# FPGA.net
KiCad netlist of a schematic drawn in Altium Designer
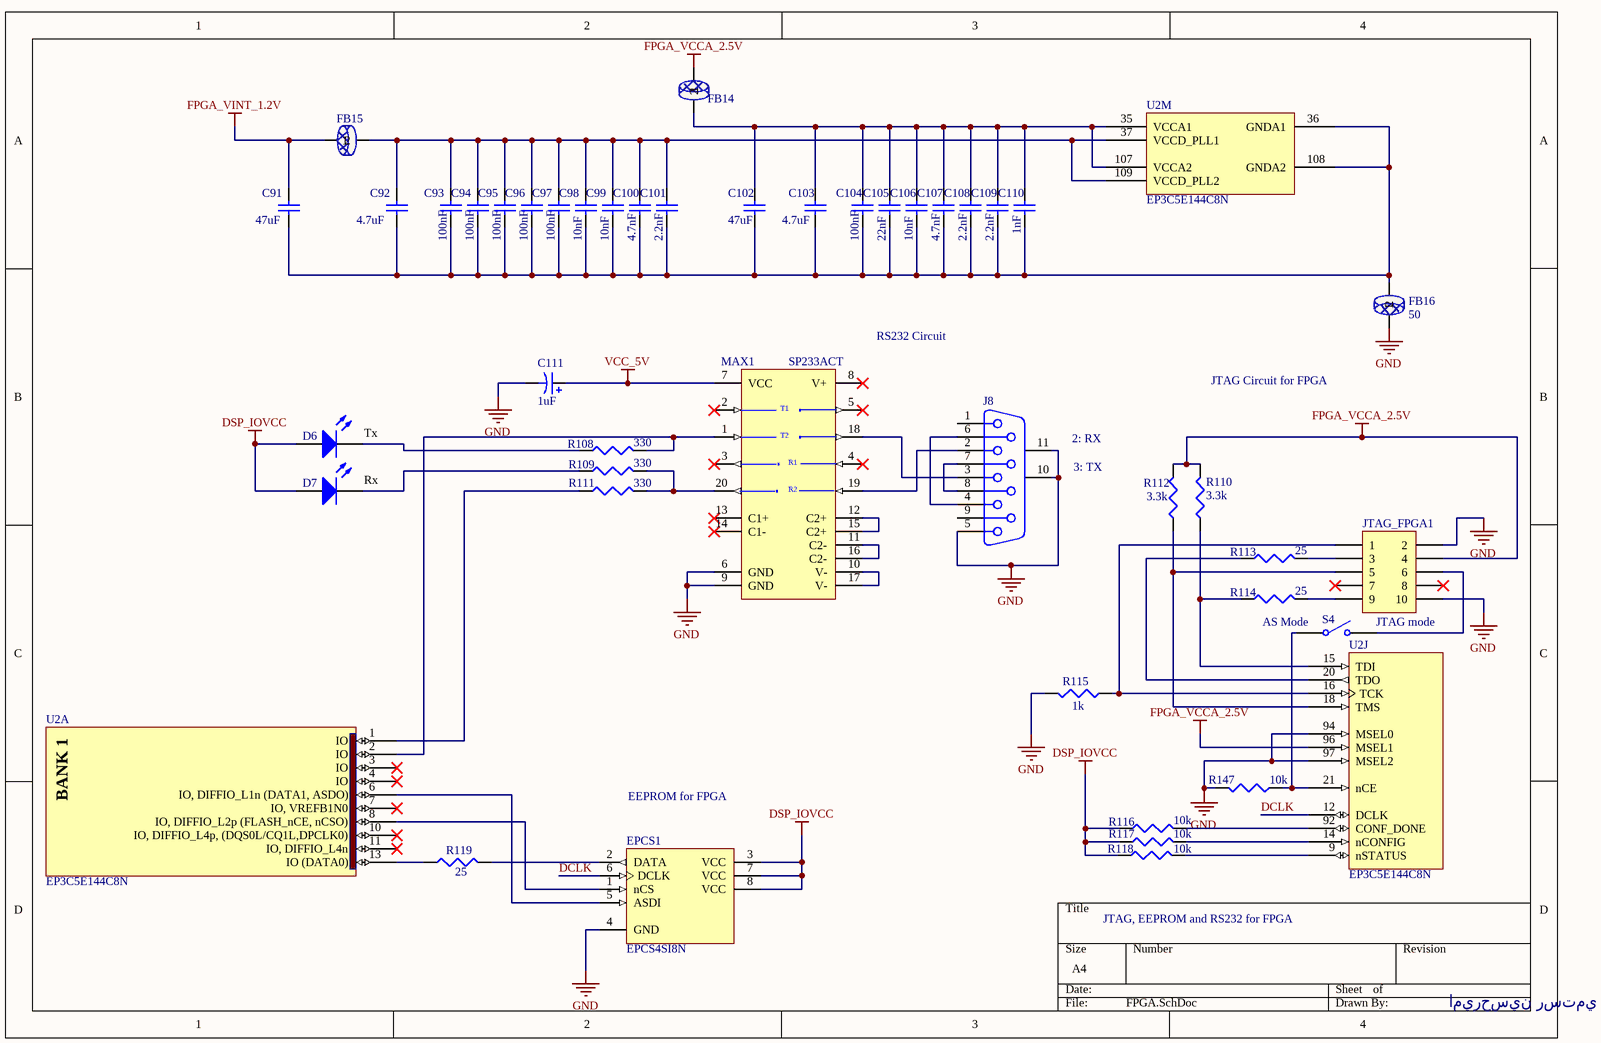
[diagram p0: FPGA.SchDoc]

(export (version "E")
  (design (tool "Eeschema 10.0.6"))
  (components
    (comp (ref "C91")
      (value "47uF")
      (footprint "C1206")
      (description "Capacitor")
      (fields (field (name "Comment") "470uF") (field (name "PUBLISHER") "Altium Limited"))
      (libsource (lib "Miscellaneous Devices") (part "Cap Semi"))
    )
    (comp (ref "C92")
      (value "4.7uF")
      (footprint "1608[0603]")
      (description "Capacitor")
      (fields (field (name "PUBLISHER") "Altium Limited"))
      (libsource (lib "Miscellaneous Devices") (part "Cap Semi"))
    )
    (comp (ref "C93")
      (value "100nF")
      (footprint "1608[0603]")
      (description "Capacitor")
      (fields (field (name "PUBLISHER") "Altium Limited"))
      (libsource (lib "Miscellaneous Devices") (part "Cap Semi"))
    )
    (comp (ref "C94")
      (value "100nF")
      (footprint "1608[0603]")
      (description "Capacitor")
      (fields (field (name "PUBLISHER") "Altium Limited"))
      (libsource (lib "Miscellaneous Devices") (part "Cap Semi"))
    )
    (comp (ref "C95")
      (value "100nF")
      (footprint "1608[0603]")
      (description "Capacitor")
      (fields (field (name "PUBLISHER") "Altium Limited"))
      (libsource (lib "Miscellaneous Devices") (part "Cap Semi"))
    )
    (comp (ref "C96")
      (value "100nF")
      (footprint "1608[0603]")
      (description "Capacitor")
      (fields (field (name "PUBLISHER") "Altium Limited"))
      (libsource (lib "Miscellaneous Devices") (part "Cap Semi"))
    )
    (comp (ref "C97")
      (value "100nF")
      (footprint "1608[0603]")
      (description "Capacitor")
      (fields (field (name "PUBLISHER") "Altium Limited"))
      (libsource (lib "Miscellaneous Devices") (part "Cap Semi"))
    )
    (comp (ref "C98")
      (value "10nF")
      (footprint "1608[0603]")
      (description "Capacitor")
      (fields (field (name "PUBLISHER") "Altium Limited"))
      (libsource (lib "Miscellaneous Devices") (part "Cap Semi"))
    )
    (comp (ref "C99")
      (value "10nF")
      (footprint "1608[0603]")
      (description "Capacitor")
      (fields (field (name "PUBLISHER") "Altium Limited"))
      (libsource (lib "Miscellaneous Devices") (part "Cap Semi"))
    )
    (comp (ref "C100")
      (value "4.7nF")
      (footprint "1608[0603]")
      (description "Capacitor")
      (fields (field (name "PUBLISHER") "Altium Limited"))
      (libsource (lib "Miscellaneous Devices") (part "Cap Semi"))
    )
    (comp (ref "C101")
      (value "2.2nF")
      (footprint "1608[0603]")
      (description "Capacitor")
      (fields (field (name "PUBLISHER") "Altium Limited"))
      (libsource (lib "Miscellaneous Devices") (part "Cap Semi"))
    )
    (comp (ref "C102")
      (value "47uF")
      (footprint "C1206")
      (description "Capacitor")
      (fields (field (name "PUBLISHER") "Altium Limited"))
      (libsource (lib "Miscellaneous Devices") (part "Cap Semi"))
    )
    (comp (ref "C103")
      (value "4.7uF")
      (footprint "1608[0603]")
      (description "Capacitor")
      (fields (field (name "PUBLISHER") "Altium Limited"))
      (libsource (lib "Miscellaneous Devices") (part "Cap Semi"))
    )
    (comp (ref "C104")
      (value "100nF")
      (footprint "1608[0603]")
      (description "Capacitor")
      (fields (field (name "PUBLISHER") "Altium Limited"))
      (libsource (lib "Miscellaneous Devices") (part "Cap Semi"))
    )
    (comp (ref "C105")
      (value "22nF")
      (footprint "1608[0603]")
      (description "Capacitor")
      (fields (field (name "PUBLISHER") "Altium Limited"))
      (libsource (lib "Miscellaneous Devices") (part "Cap Semi"))
    )
    (comp (ref "C106")
      (value "10nF")
      (footprint "1608[0603]")
      (description "Capacitor")
      (fields (field (name "PUBLISHER") "Altium Limited"))
      (libsource (lib "Miscellaneous Devices") (part "Cap Semi"))
    )
    (comp (ref "C107")
      (value "4.7nF")
      (footprint "1608[0603]")
      (description "Capacitor")
      (fields (field (name "PUBLISHER") "Altium Limited"))
      (libsource (lib "Miscellaneous Devices") (part "Cap Semi"))
    )
    (comp (ref "C108")
      (value "2.2nF")
      (footprint "1608[0603]")
      (description "Capacitor")
      (fields (field (name "PUBLISHER") "Altium Limited"))
      (libsource (lib "Miscellaneous Devices") (part "Cap Semi"))
    )
    (comp (ref "C109")
      (value "2.2nF")
      (footprint "1608[0603]")
      (description "Capacitor")
      (fields (field (name "PUBLISHER") "Altium Limited"))
      (libsource (lib "Miscellaneous Devices") (part "Cap Semi"))
    )
    (comp (ref "C110")
      (value "1nF")
      (footprint "1608[0603]")
      (description "Capacitor")
      (fields (field (name "PUBLISHER") "Altium Limited"))
      (libsource (lib "Miscellaneous Devices") (part "Cap Semi"))
    )
    (comp (ref "C111")
      (value "1uF")
      (footprint "C1206")
      (description "Polarized Capacitor")
      (fields (field (name "PUBLISHER") "Altium Limited"))
      (libsource (lib "Miscellaneous Devices") (part "Cap Pol3"))
    )
    (comp (ref "D6")
      (value "Yellow")
      (footprint "1.6X0.8X0.4")
      (description "LED")
      (fields (field (name "PUBLISHER") "Altium Limited"))
      (libsource (lib "Miscellaneous Devices") (part "LED3"))
    )
    (comp (ref "D7")
      (value "Yellow")
      (footprint "1.6X0.8X0.4")
      (description "LED")
      (fields (field (name "PUBLISHER") "Altium Limited"))
      (libsource (lib "Miscellaneous Devices") (part "LED3"))
    )
    (comp (ref "EPCS1")
      (value "EPCS4SI8N")
      (footprint "SOIC8_M")
      (fields (field (name "PUBLISHER") "Altium Limited"))
      (libsource (lib "Altera EPCS Configuration Device") (part "EPCS4SI8N"))
    )
    (comp (ref "FB14")
      (value "Ferrite Bead")
      (footprint "Miscellaneous Devices:3216[1206]")
      (libsource (lib "") (part "Ferrite Bead_1"))
    )
    (comp (ref "FB15")
      (value "50")
      (footprint "Miscellaneous Devices:3216[1206]")
      (description "Ferrite Bead")
      (libsource (lib "ferrite_bead") (part "Ferrite Bead"))
    )
    (comp (ref "FB16")
      (value "50")
      (footprint "Miscellaneous Devices:3216[1206]")
      (description "Ferrite Bead")
      (libsource (lib "") (part "Ferrite Bead_2"))
    )
    (comp (ref "J8")
      (value "D Connector 9")
      (footprint "DSUB1.385-2H9")
      (description "Receptacle Assembly, 9 Position, Right Angle")
      (fields (field (name "PUBLISHER") "Altium Limited"))
      (libsource (lib "Miscellaneous Connectors") (part "D Connector 9"))
    )
    (comp (ref "JTAG_FPGA1")
      (value "Header 5X2")
      (footprint "HDR2X5")
      (description "Header, 5-Pin, Dual row")
      (fields (field (name "PUBLISHER") "Altium Limited"))
      (libsource (lib "Miscellaneous Connectors") (part "Header 5X2"))
    )
    (comp (ref "MAX1")
      (value "SP233ACT")
      (footprint "WSO20_L")
      (description "+5V-Powered, Multichannel RS-232 Driver/Receiver")
      (fields (field (name "PUBLISHER") "Altium Limited"))
      (libsource (lib "Maxim Communication Transceiver") (part "MAX233AEWP"))
    )
    (comp (ref "R108")
      (value "330")
      (footprint "J1-0603")
      (description "Resistor")
      (fields (field (name "PUBLISHER") "Altium Limited"))
      (libsource (lib "Miscellaneous Devices") (part "Res3"))
    )
    (comp (ref "R109")
      (value "330")
      (footprint "J1-0603")
      (description "Resistor")
      (fields (field (name "PUBLISHER") "Altium Limited"))
      (libsource (lib "Miscellaneous Devices") (part "Res3"))
    )
    (comp (ref "R110")
      (value "3.3k")
      (footprint "J1-0603")
      (description "Resistor")
      (fields (field (name "PUBLISHER") "Altium Limited"))
      (libsource (lib "Miscellaneous Devices") (part "Res3"))
    )
    (comp (ref "R111")
      (value "330")
      (footprint "J1-0603")
      (description "Resistor")
      (fields (field (name "PUBLISHER") "Altium Limited"))
      (libsource (lib "Miscellaneous Devices") (part "Res3"))
    )
    (comp (ref "R112")
      (value "3.3k")
      (footprint "J1-0603")
      (description "Resistor")
      (fields (field (name "PUBLISHER") "Altium Limited"))
      (libsource (lib "Miscellaneous Devices") (part "Res3"))
    )
    (comp (ref "R113")
      (value "25")
      (footprint "J1-0603")
      (description "Resistor")
      (fields (field (name "PUBLISHER") "Altium Limited"))
      (libsource (lib "Miscellaneous Devices") (part "Res3"))
    )
    (comp (ref "R114")
      (value "25")
      (footprint "J1-0603")
      (description "Resistor")
      (fields (field (name "PUBLISHER") "Altium Limited"))
      (libsource (lib "Miscellaneous Devices") (part "Res3"))
    )
    (comp (ref "R115")
      (value "1k")
      (footprint "J1-0603")
      (description "Resistor")
      (fields (field (name "PUBLISHER") "Altium Limited"))
      (libsource (lib "Miscellaneous Devices") (part "Res3"))
    )
    (comp (ref "R116")
      (value "10k")
      (footprint "J1-0603")
      (description "Resistor")
      (fields (field (name "PUBLISHER") "Altium Limited"))
      (libsource (lib "Miscellaneous Devices") (part "Res3"))
    )
    (comp (ref "R117")
      (value "10k")
      (footprint "J1-0603")
      (description "Resistor")
      (fields (field (name "PUBLISHER") "Altium Limited"))
      (libsource (lib "Miscellaneous Devices") (part "Res3"))
    )
    (comp (ref "R118")
      (value "10k")
      (footprint "J1-0603")
      (description "Resistor")
      (fields (field (name "PUBLISHER") "Altium Limited"))
      (libsource (lib "Miscellaneous Devices") (part "Res3"))
    )
    (comp (ref "R119")
      (value "25")
      (footprint "J1-0603")
      (description "Resistor")
      (fields (field (name "PUBLISHER") "Altium Limited"))
      (libsource (lib "Miscellaneous Devices") (part "Res3"))
    )
    (comp (ref "R147")
      (value "10k")
      (footprint "J1-0603")
      (description "Resistor")
      (fields (field (name "PUBLISHER") "Altium Limited"))
      (libsource (lib "Miscellaneous Devices") (part "Res3"))
    )
    (comp (ref "S4")
      (value "SW-SPST")
      (footprint "DIP_SW_1")
      (description "Single-Pole, Single-Throw Switch")
      (fields (field (name "PUBLISHER") "Altium Limited"))
      (libsource (lib "Miscellaneous Devices") (part "SW-SPST"))
    )
    (comp (ref "U2")
      (value "EP3C5E144C8N")
      (footprint "EQFP144_N")
      (fields (field (name "PUBLISHER") "Altium Limited"))
      (libsource (lib "Altera Cyclone III") (part "EP3C5E144C8N"))
    )
  )
  (nets
    (net (code "1") (name "/DCLK") (class "Default")
      (node (ref "EPCS1") (pin "6") (pinfunction "DCLK_6") (pintype "input"))
      (node (ref "U2") (pin "12") (pinfunction "DCLK_12") (pintype "bidirectional"))
    )
    (net (code "2") (name "DSP_IOVCC") (class "Default")
      (node (ref "D6") (pin "1") (pinfunction "A_1") (pintype "passive"))
      (node (ref "D7") (pin "1") (pinfunction "A_1") (pintype "passive"))
      (node (ref "EPCS1") (pin "3") (pinfunction "VCC_3") (pintype "power_in"))
      (node (ref "EPCS1") (pin "7") (pinfunction "VCC_7") (pintype "power_in"))
      (node (ref "EPCS1") (pin "8") (pinfunction "VCC_8") (pintype "power_in"))
      (node (ref "R116") (pin "1") (pinfunction "1_1") (pintype "passive"))
      (node (ref "R117") (pin "1") (pinfunction "1_1") (pintype "passive"))
      (node (ref "R118") (pin "1") (pinfunction "1_1") (pintype "passive"))
    )
    (net (code "3") (name "FPGA_VCCA_2.5V") (class "Default")
      (node (ref "FB14") (pin "2") (pinfunction "2_2") (pintype "passive"))
      (node (ref "JTAG_FPGA1") (pin "4") (pinfunction "4_4") (pintype "passive"))
      (node (ref "R110") (pin "2") (pinfunction "2_2") (pintype "passive"))
      (node (ref "R112") (pin "2") (pinfunction "2_2") (pintype "passive"))
      (node (ref "U2") (pin "96") (pinfunction "MSEL1_96") (pintype "input"))
    )
    (net (code "4") (name "FPGA_VINT_1.2V") (class "Default")
      (node (ref "C91") (pin "1") (pinfunction "1_1") (pintype "passive"))
      (node (ref "FB15") (pin "2") (pinfunction "2_2") (pintype "passive"))
    )
    (net (code "5") (name "GND") (class "Default")
      (node (ref "C111") (pin "2") (pinfunction "2_2") (pintype "passive"))
      (node (ref "EPCS1") (pin "4") (pinfunction "GND_4") (pintype "power_in"))
      (node (ref "FB16") (pin "2") (pinfunction "2_2") (pintype "passive"))
      (node (ref "J8") (pin "10") (pinfunction "MH1_10") (pintype "passive"))
      (node (ref "J8") (pin "11") (pinfunction "MH2_11") (pintype "passive"))
      (node (ref "J8") (pin "5") (pinfunction "5_5") (pintype "passive"))
      (node (ref "JTAG_FPGA1") (pin "10") (pinfunction "10_10") (pintype "passive"))
      (node (ref "JTAG_FPGA1") (pin "2") (pinfunction "2_2") (pintype "passive"))
      (node (ref "MAX1") (pin "6") (pinfunction "GND_6") (pintype "power_in"))
      (node (ref "MAX1") (pin "9") (pinfunction "GND_9") (pintype "power_in"))
      (node (ref "R115") (pin "2") (pinfunction "2_2") (pintype "passive"))
      (node (ref "R147") (pin "2") (pinfunction "2_2") (pintype "passive"))
      (node (ref "U2") (pin "94") (pinfunction "MSEL0_94") (pintype "input"))
      (node (ref "U2") (pin "97") (pinfunction "MSEL2_97") (pintype "input"))
    )
    (net (code "6") (name "Net-(D6-K)") (class "Default")
      (node (ref "D6") (pin "2") (pinfunction "K_2") (pintype "passive"))
      (node (ref "R108") (pin "1") (pinfunction "1_1") (pintype "passive"))
    )
    (net (code "7") (name "Net-(D7-K)") (class "Default")
      (node (ref "D7") (pin "2") (pinfunction "K_2") (pintype "passive"))
      (node (ref "R109") (pin "1") (pinfunction "1_1") (pintype "passive"))
    )
    (net (code "8") (name "Net-(EPCS1-ASDI)") (class "Default")
      (node (ref "EPCS1") (pin "5") (pinfunction "ASDI_5") (pintype "input"))
      (node (ref "U2") (pin "6") (pinfunction "IO,_DIFFIO_L1n_(DATA1,_ASDO)_6") (pintype "bidirectional"))
    )
    (net (code "9") (name "Net-(EPCS1-DATA)") (class "Default")
      (node (ref "EPCS1") (pin "2") (pinfunction "DATA_2") (pintype "output"))
      (node (ref "R119") (pin "2") (pinfunction "2_2") (pintype "passive"))
    )
    (net (code "10") (name "Net-(EPCS1-nCS)") (class "Default")
      (node (ref "EPCS1") (pin "1") (pinfunction "nCS_1") (pintype "input"))
      (node (ref "U2") (pin "8") (pinfunction "IO,_DIFFIO_L2p_(FLASH_nCE,_nCSO)_8") (pintype "bidirectional"))
    )
    (net (code "11") (name "Net-(J8-Pad4)") (class "Default")
      (node (ref "J8") (pin "4") (pinfunction "4_4") (pintype "passive"))
      (node (ref "J8") (pin "6") (pinfunction "6_6") (pintype "passive"))
    )
    (net (code "12") (name "Net-(J8-Pad7)") (class "Default")
      (node (ref "J8") (pin "7") (pinfunction "7_7") (pintype "passive"))
      (node (ref "J8") (pin "8") (pinfunction "8_8") (pintype "passive"))
    )
    (net (code "13") (name "Net-(JTAG_FPGA1-Pad3)") (class "Default")
      (node (ref "JTAG_FPGA1") (pin "3") (pinfunction "3_3") (pintype "passive"))
      (node (ref "R113") (pin "2") (pinfunction "2_2") (pintype "passive"))
    )
    (net (code "14") (name "Net-(JTAG_FPGA1-Pad9)") (class "Default")
      (node (ref "JTAG_FPGA1") (pin "9") (pinfunction "9_9") (pintype "passive"))
      (node (ref "R114") (pin "2") (pinfunction "2_2") (pintype "passive"))
    )
    (net (code "15") (name "Net-(MAX1-C2+-Pad12)") (class "Default")
      (node (ref "MAX1") (pin "12") (pinfunction "C2+_12") (pintype "power_in"))
      (node (ref "MAX1") (pin "15") (pinfunction "C2+_15") (pintype "passive"))
    )
    (net (code "16") (name "Net-(MAX1-C2--Pad11)") (class "Default")
      (node (ref "MAX1") (pin "11") (pinfunction "C2-_11") (pintype "passive"))
      (node (ref "MAX1") (pin "16") (pinfunction "C2-_16") (pintype "passive"))
    )
    (net (code "17") (name "Net-(MAX1-R2IN)") (class "Default")
      (node (ref "J8") (pin "2") (pinfunction "2_2") (pintype "passive"))
      (node (ref "MAX1") (pin "19") (pinfunction "R2IN_19") (pintype "input"))
    )
    (net (code "18") (name "Net-(MAX1-R2OUT)") (class "Default")
      (node (ref "MAX1") (pin "20") (pinfunction "R2OUT_20") (pintype "output"))
      (node (ref "R109") (pin "2") (pinfunction "2_2") (pintype "passive"))
      (node (ref "R111") (pin "2") (pinfunction "2_2") (pintype "passive"))
    )
    (net (code "19") (name "Net-(MAX1-T2IN)") (class "Default")
      (node (ref "MAX1") (pin "1") (pinfunction "T2IN_1") (pintype "input"))
      (node (ref "R108") (pin "2") (pinfunction "2_2") (pintype "passive"))
      (node (ref "U2") (pin "2") (pinfunction "IO_2") (pintype "bidirectional"))
    )
    (net (code "20") (name "Net-(MAX1-T2OUT)") (class "Default")
      (node (ref "J8") (pin "3") (pinfunction "3_3") (pintype "passive"))
      (node (ref "MAX1") (pin "18") (pinfunction "T2OUT_18") (pintype "output"))
    )
    (net (code "21") (name "Net-(MAX1-V--Pad10)") (class "Default")
      (node (ref "MAX1") (pin "10") (pinfunction "V-_10") (pintype "passive"))
      (node (ref "MAX1") (pin "17") (pinfunction "V-_17") (pintype "power_in"))
    )
    (net (code "22") (name "Net-(R111-Pad1)") (class "Default")
      (node (ref "R111") (pin "1") (pinfunction "1_1") (pintype "passive"))
      (node (ref "U2") (pin "1") (pinfunction "IO_1") (pintype "bidirectional"))
    )
    (net (code "23") (name "Net-(S4-COMMON)") (class "Default")
      (node (ref "R147") (pin "1") (pinfunction "1_1") (pintype "passive"))
      (node (ref "S4") (pin "1") (pinfunction "COMMON_1") (pintype "passive"))
      (node (ref "U2") (pin "21") (pinfunction "nCE_21") (pintype "input"))
    )
    (net (code "24") (name "Net-(S4-NO)") (class "Default")
      (node (ref "JTAG_FPGA1") (pin "6") (pinfunction "6_6") (pintype "passive"))
      (node (ref "S4") (pin "2") (pinfunction "NO_2") (pintype "passive"))
    )
    (net (code "25") (name "Net-(U2A-IO_(DATA0))") (class "Default")
      (node (ref "R119") (pin "1") (pinfunction "1_1") (pintype "passive"))
      (node (ref "U2") (pin "13") (pinfunction "IO_(DATA0)_13") (pintype "bidirectional"))
    )
    (net (code "26") (name "Net-(U2J-CONF_DONE)") (class "Default")
      (node (ref "R116") (pin "2") (pinfunction "2_2") (pintype "passive"))
      (node (ref "U2") (pin "92") (pinfunction "CONF_DONE_92") (pintype "bidirectional"))
    )
    (net (code "27") (name "Net-(U2J-TCK)") (class "Default")
      (node (ref "JTAG_FPGA1") (pin "1") (pinfunction "1_1") (pintype "passive"))
      (node (ref "R115") (pin "1") (pinfunction "1_1") (pintype "passive"))
      (node (ref "U2") (pin "16") (pinfunction "TCK_16") (pintype "input"))
    )
    (net (code "28") (name "Net-(U2J-TDI)") (class "Default")
      (node (ref "R110") (pin "1") (pinfunction "1_1") (pintype "passive"))
      (node (ref "R114") (pin "1") (pinfunction "1_1") (pintype "passive"))
      (node (ref "U2") (pin "15") (pinfunction "TDI_15") (pintype "input"))
    )
    (net (code "29") (name "Net-(U2J-TDO)") (class "Default")
      (node (ref "R113") (pin "1") (pinfunction "1_1") (pintype "passive"))
      (node (ref "U2") (pin "20") (pinfunction "TDO_20") (pintype "output"))
    )
    (net (code "30") (name "Net-(U2J-TMS)") (class "Default")
      (node (ref "JTAG_FPGA1") (pin "5") (pinfunction "5_5") (pintype "passive"))
      (node (ref "R112") (pin "1") (pinfunction "1_1") (pintype "passive"))
      (node (ref "U2") (pin "18") (pinfunction "TMS_18") (pintype "input"))
    )
    (net (code "31") (name "Net-(U2J-nCONFIG)") (class "Default")
      (node (ref "R117") (pin "2") (pinfunction "2_2") (pintype "passive"))
      (node (ref "U2") (pin "14") (pinfunction "nCONFIG_14") (pintype "input"))
    )
    (net (code "32") (name "Net-(U2J-nSTATUS)") (class "Default")
      (node (ref "R118") (pin "2") (pinfunction "2_2") (pintype "passive"))
      (node (ref "U2") (pin "9") (pinfunction "nSTATUS_9") (pintype "bidirectional"))
    )
    (net (code "33") (name "Net-(U2M-GNDA1)") (class "Default")
      (node (ref "C100") (pin "2") (pinfunction "2_2") (pintype "passive"))
      (node (ref "C101") (pin "2") (pinfunction "2_2") (pintype "passive"))
      (node (ref "C102") (pin "2") (pinfunction "2_2") (pintype "passive"))
      (node (ref "C103") (pin "2") (pinfunction "2_2") (pintype "passive"))
      (node (ref "C104") (pin "2") (pinfunction "2_2") (pintype "passive"))
      (node (ref "C105") (pin "2") (pinfunction "2_2") (pintype "passive"))
      (node (ref "C106") (pin "2") (pinfunction "2_2") (pintype "passive"))
      (node (ref "C107") (pin "2") (pinfunction "2_2") (pintype "passive"))
      (node (ref "C108") (pin "2") (pinfunction "2_2") (pintype "passive"))
      (node (ref "C109") (pin "2") (pinfunction "2_2") (pintype "passive"))
      (node (ref "C110") (pin "2") (pinfunction "2_2") (pintype "passive"))
      (node (ref "C91") (pin "2") (pinfunction "2_2") (pintype "passive"))
      (node (ref "C92") (pin "2") (pinfunction "2_2") (pintype "passive"))
      (node (ref "C93") (pin "2") (pinfunction "2_2") (pintype "passive"))
      (node (ref "C94") (pin "2") (pinfunction "2_2") (pintype "passive"))
      (node (ref "C95") (pin "2") (pinfunction "2_2") (pintype "passive"))
      (node (ref "C96") (pin "2") (pinfunction "2_2") (pintype "passive"))
      (node (ref "C97") (pin "2") (pinfunction "2_2") (pintype "passive"))
      (node (ref "C98") (pin "2") (pinfunction "2_2") (pintype "passive"))
      (node (ref "C99") (pin "2") (pinfunction "2_2") (pintype "passive"))
      (node (ref "FB16") (pin "1") (pinfunction "1_1") (pintype "passive"))
      (node (ref "U2") (pin "108") (pinfunction "GNDA2_108") (pintype "power_in"))
      (node (ref "U2") (pin "36") (pinfunction "GNDA1_36") (pintype "power_in"))
    )
    (net (code "34") (name "Net-(U2M-VCCA1)") (class "Default")
      (node (ref "C102") (pin "1") (pinfunction "1_1") (pintype "passive"))
      (node (ref "C103") (pin "1") (pinfunction "1_1") (pintype "passive"))
      (node (ref "C104") (pin "1") (pinfunction "1_1") (pintype "passive"))
      (node (ref "C105") (pin "1") (pinfunction "1_1") (pintype "passive"))
      (node (ref "C106") (pin "1") (pinfunction "1_1") (pintype "passive"))
      (node (ref "C107") (pin "1") (pinfunction "1_1") (pintype "passive"))
      (node (ref "C108") (pin "1") (pinfunction "1_1") (pintype "passive"))
      (node (ref "C109") (pin "1") (pinfunction "1_1") (pintype "passive"))
      (node (ref "C110") (pin "1") (pinfunction "1_1") (pintype "passive"))
      (node (ref "FB14") (pin "1") (pinfunction "1_1") (pintype "passive"))
      (node (ref "U2") (pin "107") (pinfunction "VCCA2_107") (pintype "power_in"))
      (node (ref "U2") (pin "35") (pinfunction "VCCA1_35") (pintype "power_in"))
    )
    (net (code "35") (name "Net-(U2M-VCCD_PLL1)") (class "Default")
      (node (ref "C100") (pin "1") (pinfunction "1_1") (pintype "passive"))
      (node (ref "C101") (pin "1") (pinfunction "1_1") (pintype "passive"))
      (node (ref "C92") (pin "1") (pinfunction "1_1") (pintype "passive"))
      (node (ref "C93") (pin "1") (pinfunction "1_1") (pintype "passive"))
      (node (ref "C94") (pin "1") (pinfunction "1_1") (pintype "passive"))
      (node (ref "C95") (pin "1") (pinfunction "1_1") (pintype "passive"))
      (node (ref "C96") (pin "1") (pinfunction "1_1") (pintype "passive"))
      (node (ref "C97") (pin "1") (pinfunction "1_1") (pintype "passive"))
      (node (ref "C98") (pin "1") (pinfunction "1_1") (pintype "passive"))
      (node (ref "C99") (pin "1") (pinfunction "1_1") (pintype "passive"))
      (node (ref "FB15") (pin "1") (pinfunction "1_1") (pintype "passive"))
      (node (ref "U2") (pin "109") (pinfunction "VCCD_PLL2_109") (pintype "power_in"))
      (node (ref "U2") (pin "37") (pinfunction "VCCD_PLL1_37") (pintype "power_in"))
    )
    (net (code "36") (name "VCC_5V") (class "Default")
      (node (ref "C111") (pin "1") (pinfunction "1_1") (pintype "passive"))
      (node (ref "MAX1") (pin "7") (pinfunction "VCC_7") (pintype "power_in"))
    )
    (net (code "37") (name "unconnected-(J8-Pad1)") (class "Default")
      (node (ref "J8") (pin "1") (pinfunction "1_1") (pintype "passive"))
    )
    (net (code "38") (name "unconnected-(J8-Pad9)") (class "Default")
      (node (ref "J8") (pin "9") (pinfunction "9_9") (pintype "passive"))
    )
    (net (code "39") (name "unconnected-(JTAG_FPGA1-Pad7)") (class "Default")
      (node (ref "JTAG_FPGA1") (pin "7") (pinfunction "7_7") (pintype "passive+no_connect"))
    )
    (net (code "40") (name "unconnected-(JTAG_FPGA1-Pad8)") (class "Default")
      (node (ref "JTAG_FPGA1") (pin "8") (pinfunction "8_8") (pintype "passive+no_connect"))
    )
    (net (code "41") (name "unconnected-(MAX1-C1+-Pad13)") (class "Default")
      (node (ref "MAX1") (pin "13") (pinfunction "C1+_13") (pintype "passive+no_connect"))
    )
    (net (code "42") (name "unconnected-(MAX1-C1--Pad14)") (class "Default")
      (node (ref "MAX1") (pin "14") (pinfunction "C1-_14") (pintype "power_in+no_connect"))
    )
    (net (code "43") (name "unconnected-(MAX1-R1IN-Pad4)") (class "Default")
      (node (ref "MAX1") (pin "4") (pinfunction "R1IN_4") (pintype "input+no_connect"))
    )
    (net (code "44") (name "unconnected-(MAX1-R1OUT-Pad3)") (class "Default")
      (node (ref "MAX1") (pin "3") (pinfunction "R1OUT_3") (pintype "output+no_connect"))
    )
    (net (code "45") (name "unconnected-(MAX1-T1IN-Pad2)") (class "Default")
      (node (ref "MAX1") (pin "2") (pinfunction "T1IN_2") (pintype "input+no_connect"))
    )
    (net (code "46") (name "unconnected-(MAX1-T1OUT-Pad5)") (class "Default")
      (node (ref "MAX1") (pin "5") (pinfunction "T1OUT_5") (pintype "output+no_connect"))
    )
    (net (code "47") (name "unconnected-(MAX1-V+-Pad8)") (class "Default")
      (node (ref "MAX1") (pin "8") (pinfunction "V+_8") (pintype "passive+no_connect"))
    )
    (net (code "48") (name "unconnected-(U2A-IO,_DIFFIO_L4n-Pad11)") (class "Default")
      (node (ref "U2") (pin "11") (pinfunction "IO,_DIFFIO_L4n_11") (pintype "bidirectional+no_connect"))
    )
    (net (code "49") (name "unconnected-(U2A-IO,_DIFFIO_L4p,_(DQS0L{slash}CQ1L,DPCLK0)-Pad10)") (class "Default")
      (node (ref "U2") (pin "10") (pinfunction "IO,_DIFFIO_L4p,_(DQS0L/CQ1L,DPCLK0)_10") (pintype "bidirectional+no_connect"))
    )
    (net (code "50") (name "unconnected-(U2A-IO,_VREFB1N0-Pad7)") (class "Default")
      (node (ref "U2") (pin "7") (pinfunction "IO,_VREFB1N0_7") (pintype "bidirectional+no_connect"))
    )
    (net (code "51") (name "unconnected-(U2A-IO-Pad3)") (class "Default")
      (node (ref "U2") (pin "3") (pinfunction "IO_3") (pintype "bidirectional+no_connect"))
    )
    (net (code "52") (name "unconnected-(U2A-IO-Pad4)") (class "Default")
      (node (ref "U2") (pin "4") (pinfunction "IO_4") (pintype "bidirectional+no_connect"))
    )
  )
)
